# Relay_Control.net
KiCad netlist of a schematic drawn in Altium Designer
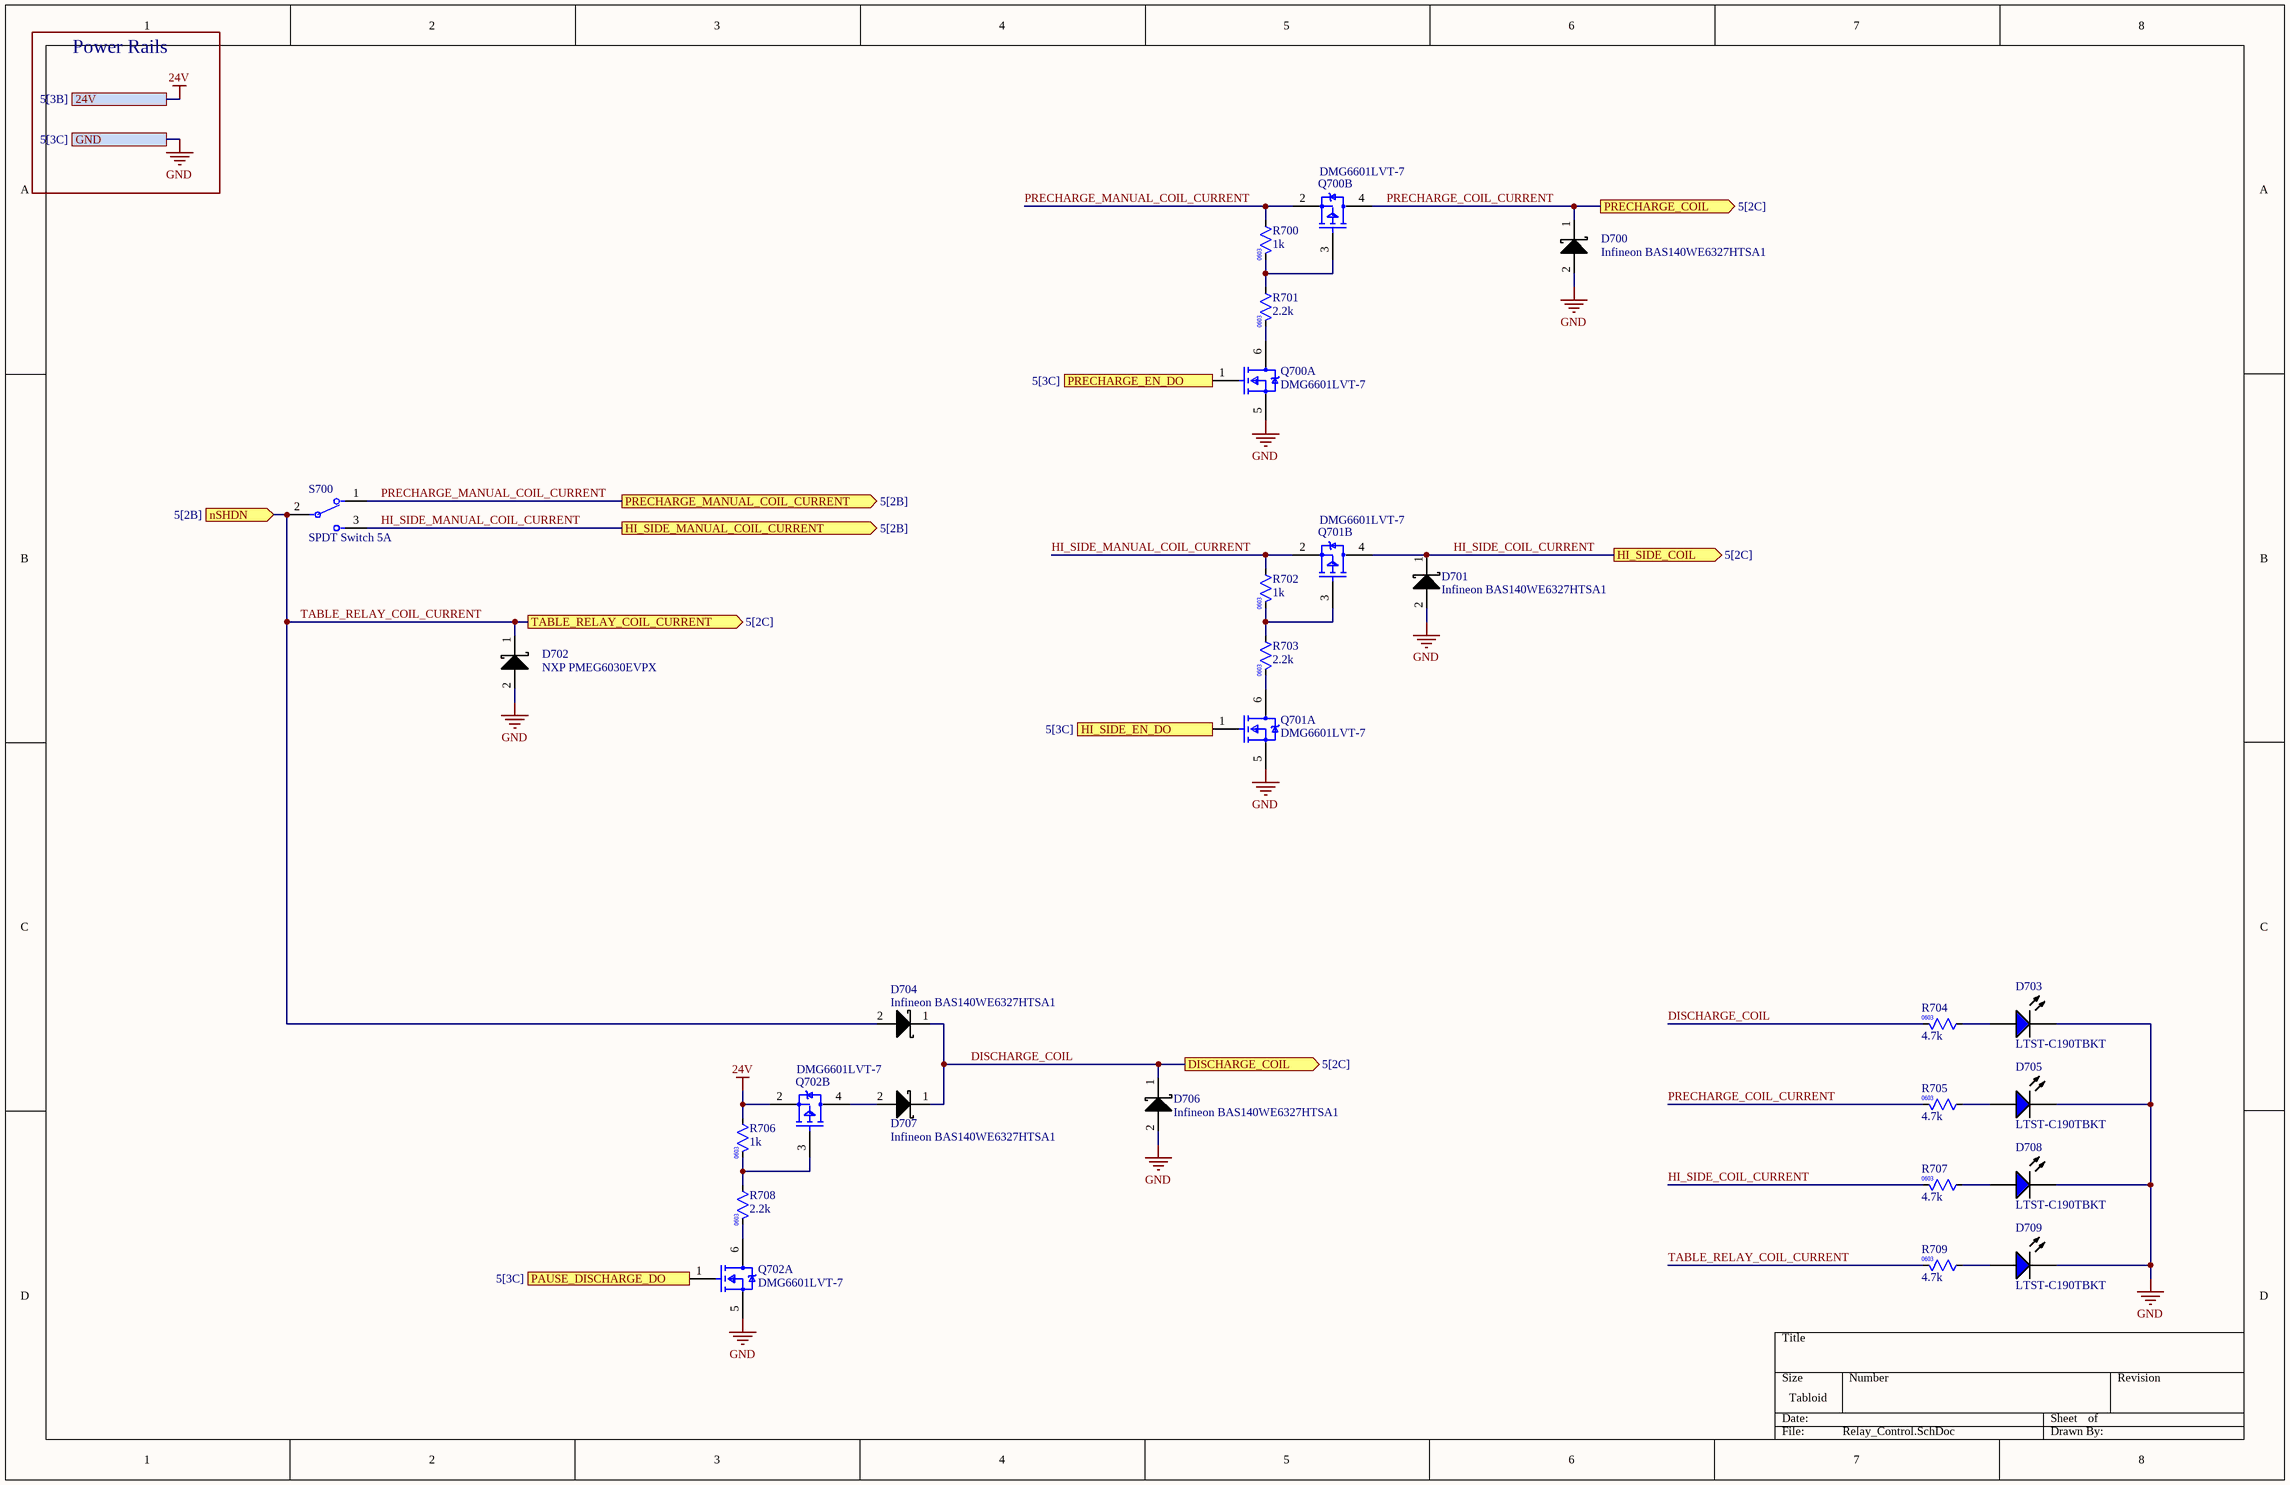
[diagram p0: Relay_Control.SchDoc]

(export (version "E")
  (design (tool "Eeschema 10.0.6"))
  (components
    (comp (ref "D700")
      (value "Infineon BAS140WE6327HTSA1")
      (footprint "INFINEON BAS140W SERIES")
      (description "DIODE SCHOTTKY 40V 120MA SOD323")
      (fields (field (name "SOURCE") "UBC Formula Electric.SchLib"))
      (libsource (lib "UBC Formula Electric") (part "Symbol"))
    )
    (comp (ref "D701")
      (value "Infineon BAS140WE6327HTSA1")
      (footprint "INFINEON BAS140W SERIES")
      (description "DIODE SCHOTTKY 40V 120MA SOD323")
      (fields (field (name "SOURCE") "UBC Formula Electric.SchLib"))
      (libsource (lib "UBC Formula Electric") (part "Symbol"))
    )
    (comp (ref "D702")
      (value "NXP PMEG6030EVPX")
      (footprint "NXP PMEG6030EVPX")
      (description "Diode Schottky 60V 3A Surface Mount SOD-128/CFP5")
      (fields (field (name "SOURCE") "Quad_Inverter.SchLib"))
      (libsource (lib "") (part "Symbol_1"))
    )
    (comp (ref "D703")
      (value "LTST-C190TBKT")
      (footprint "LTST-C190TBKT-2_V")
      (description "LED Uni-Color Blue, 76 mW, 20 mA, -20 to 80 degC, 2-Pin SMD, RoHS, Tape and Reel")
      (fields (field (name "MANUFACTURER") "Lite-On"))
      (libsource (lib "UBC Formula Electric") (part "LED-BLUE-AK-2"))
    )
    (comp (ref "D704")
      (value "Infineon BAS140WE6327HTSA1")
      (footprint "INFINEON BAS140W SERIES")
      (description "DIODE SCHOTTKY 40V 120MA SOD323")
      (fields (field (name "SOURCE") "UBC Formula Electric.SchLib"))
      (libsource (lib "UBC Formula Electric") (part "Symbol"))
    )
    (comp (ref "D705")
      (value "LTST-C190TBKT")
      (footprint "LTST-C190TBKT-2_V")
      (description "LED Uni-Color Blue, 76 mW, 20 mA, -20 to 80 degC, 2-Pin SMD, RoHS, Tape and Reel")
      (fields (field (name "MANUFACTURER") "Lite-On"))
      (libsource (lib "UBC Formula Electric") (part "LED-BLUE-AK-2"))
    )
    (comp (ref "D706")
      (value "Infineon BAS140WE6327HTSA1")
      (footprint "INFINEON BAS140W SERIES")
      (description "DIODE SCHOTTKY 40V 120MA SOD323")
      (fields (field (name "SOURCE") "UBC Formula Electric.SchLib"))
      (libsource (lib "UBC Formula Electric") (part "Symbol"))
    )
    (comp (ref "D707")
      (value "Infineon BAS140WE6327HTSA1")
      (footprint "INFINEON BAS140W SERIES")
      (description "DIODE SCHOTTKY 40V 120MA SOD323")
      (fields (field (name "SOURCE") "UBC Formula Electric.SchLib"))
      (libsource (lib "UBC Formula Electric") (part "Symbol"))
    )
    (comp (ref "D708")
      (value "LTST-C190TBKT")
      (footprint "LTST-C190TBKT-2_V")
      (description "LED Uni-Color Blue, 76 mW, 20 mA, -20 to 80 degC, 2-Pin SMD, RoHS, Tape and Reel")
      (fields (field (name "MANUFACTURER") "Lite-On"))
      (libsource (lib "UBC Formula Electric") (part "LED-BLUE-AK-2"))
    )
    (comp (ref "D709")
      (value "LTST-C190TBKT")
      (footprint "LTST-C190TBKT-2_V")
      (description "LED Uni-Color Blue, 76 mW, 20 mA, -20 to 80 degC, 2-Pin SMD, RoHS, Tape and Reel")
      (fields (field (name "MANUFACTURER") "Lite-On"))
      (libsource (lib "UBC Formula Electric") (part "LED-BLUE-AK-2"))
    )
    (comp (ref "Q700")
      (value "DMG6601LVT-7")
      (footprint "FP-TSOT26-IPC_A")
      (libsource (lib "UBC Formula Electric") (part "06fe37a93ab8884fb11e636f76dd7e0"))
    )
    (comp (ref "Q701")
      (value "DMG6601LVT-7")
      (footprint "FP-TSOT26-IPC_A")
      (libsource (lib "UBC Formula Electric") (part "06fe37a93ab8884fb11e636f76dd7e0"))
    )
    (comp (ref "Q702")
      (value "DMG6601LVT-7")
      (footprint "FP-TSOT26-IPC_A")
      (libsource (lib "UBC Formula Electric") (part "06fe37a93ab8884fb11e636f76dd7e0"))
    )
    (comp (ref "R700")
      (value "1k")
      (footprint "0603 Resistor Footprint")
      (description "RES SMD 1K OHM 1% 1/3W 0603")
      (fields (field (name "TOLERANCE") "1%") (field (name "POWER") "250mW"))
      (libsource (lib "UBC Formula Electric") (part "RES-2"))
    )
    (comp (ref "R701")
      (value "2.2k")
      (footprint "0603 Resistor Footprint")
      (description "RES SMD 2.2K OHM 1% 1/4W 0603")
      (fields
        (field (name "DIGIKEY PART NUMBER") "541-10449-1-ND")
        (field (name "MANUFACTURER PART NUMBER") "RCS06032K20FKEA")
      )
      (libsource (lib "UBC Formula Electric") (part "RES-2"))
    )
    (comp (ref "R702")
      (value "1k")
      (footprint "0603 Resistor Footprint")
      (description "RES SMD 1K OHM 1% 1/3W 0603")
      (fields (field (name "TOLERANCE") "1%") (field (name "POWER") "250mW"))
      (libsource (lib "UBC Formula Electric") (part "RES-2"))
    )
    (comp (ref "R703")
      (value "2.2k")
      (footprint "0603 Resistor Footprint")
      (description "RES SMD 2.2K OHM 1% 1/4W 0603")
      (fields
        (field (name "DIGIKEY PART NUMBER") "541-10449-1-ND")
        (field (name "MANUFACTURER PART NUMBER") "RCS06032K20FKEA")
      )
      (libsource (lib "UBC Formula Electric") (part "RES-2"))
    )
    (comp (ref "R704")
      (value "4.7k")
      (footprint "0603 Resistor Footprint")
      (description "RES SMD 4.7K OHM 1% 1/3W 0603")
      (fields (field (name "TOLERANCE") "1%") (field (name "POWER") "250mW"))
      (libsource (lib "UBC Formula Electric") (part "RES-2"))
    )
    (comp (ref "R705")
      (value "4.7k")
      (footprint "0603 Resistor Footprint")
      (description "RES SMD 4.7K OHM 1% 1/3W 0603")
      (fields (field (name "TOLERANCE") "1%") (field (name "POWER") "250mW"))
      (libsource (lib "UBC Formula Electric") (part "RES-2"))
    )
    (comp (ref "R706")
      (value "1k")
      (footprint "0603 Resistor Footprint")
      (description "RES SMD 1K OHM 1% 1/3W 0603")
      (fields (field (name "TOLERANCE") "1%") (field (name "POWER") "250mW"))
      (libsource (lib "UBC Formula Electric") (part "RES-2"))
    )
    (comp (ref "R707")
      (value "4.7k")
      (footprint "0603 Resistor Footprint")
      (description "RES SMD 4.7K OHM 1% 1/3W 0603")
      (fields (field (name "TOLERANCE") "1%") (field (name "POWER") "250mW"))
      (libsource (lib "UBC Formula Electric") (part "RES-2"))
    )
    (comp (ref "R708")
      (value "2.2k")
      (footprint "0603 Resistor Footprint")
      (description "RES SMD 2.2K OHM 1% 1/4W 0603")
      (fields
        (field (name "DIGIKEY PART NUMBER") "541-10449-1-ND")
        (field (name "MANUFACTURER PART NUMBER") "RCS06032K20FKEA")
      )
      (libsource (lib "UBC Formula Electric") (part "RES-2"))
    )
    (comp (ref "R709")
      (value "4.7k")
      (footprint "0603 Resistor Footprint")
      (description "RES SMD 4.7K OHM 1% 1/3W 0603")
      (fields (field (name "TOLERANCE") "1%") (field (name "POWER") "250mW"))
      (libsource (lib "UBC Formula Electric") (part "RES-2"))
    )
    (comp (ref "S700")
      (value "SPDT Switch 5A")
      (footprint "SPDT 5A")
      (libsource (lib "air_hockey_lib") (part "SPDT Switch 5A"))
    )
  )
  (nets
    (net (code "1") (name "/DISCHARGE_COIL") (class "Default")
      (node (ref "D704") (pin "1") (pinfunction "1_1") (pintype "passive"))
      (node (ref "D706") (pin "1") (pinfunction "1_1") (pintype "passive"))
      (node (ref "D707") (pin "1") (pinfunction "1_1") (pintype "passive"))
      (node (ref "R704") (pin "2") (pinfunction "2_2") (pintype "passive"))
    )
    (net (code "2") (name "/HI_SIDE_COIL_CURRENT") (class "Default")
      (node (ref "D701") (pin "1") (pinfunction "1_1") (pintype "passive"))
      (node (ref "Q701") (pin "4") (pinfunction "D2_4") (pintype "passive"))
      (node (ref "R707") (pin "2") (pinfunction "2_2") (pintype "passive"))
    )
    (net (code "3") (name "/HI_SIDE_EN_DO") (class "Default")
      (node (ref "Q701") (pin "1") (pinfunction "G1_1") (pintype "passive"))
    )
    (net (code "4") (name "/HI_SIDE_MANUAL_COIL_CURRENT") (class "Default")
      (node (ref "Q701") (pin "2") (pinfunction "S2_2") (pintype "passive"))
      (node (ref "R702") (pin "1") (pinfunction "1_1") (pintype "passive"))
      (node (ref "S700") (pin "3") (pinfunction "3_3") (pintype "passive"))
    )
    (net (code "5") (name "/PAUSE_DISCHARGE_DO") (class "Default")
      (node (ref "Q702") (pin "1") (pinfunction "G1_1") (pintype "passive"))
    )
    (net (code "6") (name "/PRECHARGE_COIL_CURRENT") (class "Default")
      (node (ref "D700") (pin "1") (pinfunction "1_1") (pintype "passive"))
      (node (ref "Q700") (pin "4") (pinfunction "D2_4") (pintype "passive"))
      (node (ref "R705") (pin "2") (pinfunction "2_2") (pintype "passive"))
    )
    (net (code "7") (name "/PRECHARGE_EN_DO") (class "Default")
      (node (ref "Q700") (pin "1") (pinfunction "G1_1") (pintype "passive"))
    )
    (net (code "8") (name "/PRECHARGE_MANUAL_COIL_CURRENT") (class "Default")
      (node (ref "Q700") (pin "2") (pinfunction "S2_2") (pintype "passive"))
      (node (ref "R700") (pin "1") (pinfunction "1_1") (pintype "passive"))
      (node (ref "S700") (pin "1") (pinfunction "1_1") (pintype "passive"))
    )
    (net (code "9") (name "/TABLE_RELAY_COIL_CURRENT") (class "Default")
      (node (ref "D702") (pin "1") (pinfunction "1_1") (pintype "passive"))
      (node (ref "D704") (pin "2") (pinfunction "2_2") (pintype "passive"))
      (node (ref "R709") (pin "2") (pinfunction "2_2") (pintype "passive"))
      (node (ref "S700") (pin "2") (pinfunction "2_2") (pintype "passive"))
    )
    (net (code "10") (name "24V") (class "Default")
      (node (ref "Q702") (pin "2") (pinfunction "S2_2") (pintype "passive"))
      (node (ref "R706") (pin "1") (pinfunction "1_1") (pintype "passive"))
    )
    (net (code "11") (name "GND") (class "Default")
      (node (ref "D700") (pin "2") (pinfunction "2_2") (pintype "passive"))
      (node (ref "D701") (pin "2") (pinfunction "2_2") (pintype "passive"))
      (node (ref "D702") (pin "2") (pinfunction "2_2") (pintype "passive"))
      (node (ref "D703") (pin "2") (pinfunction "K_2") (pintype "passive"))
      (node (ref "D705") (pin "2") (pinfunction "K_2") (pintype "passive"))
      (node (ref "D706") (pin "2") (pinfunction "2_2") (pintype "passive"))
      (node (ref "D708") (pin "2") (pinfunction "K_2") (pintype "passive"))
      (node (ref "D709") (pin "2") (pinfunction "K_2") (pintype "passive"))
      (node (ref "Q700") (pin "5") (pinfunction "S1_5") (pintype "passive"))
      (node (ref "Q701") (pin "5") (pinfunction "S1_5") (pintype "passive"))
      (node (ref "Q702") (pin "5") (pinfunction "S1_5") (pintype "passive"))
    )
    (net (code "12") (name "Net-(D703-A)") (class "Default")
      (node (ref "D703") (pin "1") (pinfunction "A_1") (pintype "passive"))
      (node (ref "R704") (pin "1") (pinfunction "1_1") (pintype "passive"))
    )
    (net (code "13") (name "Net-(D705-A)") (class "Default")
      (node (ref "D705") (pin "1") (pinfunction "A_1") (pintype "passive"))
      (node (ref "R705") (pin "1") (pinfunction "1_1") (pintype "passive"))
    )
    (net (code "14") (name "Net-(D708-A)") (class "Default")
      (node (ref "D708") (pin "1") (pinfunction "A_1") (pintype "passive"))
      (node (ref "R707") (pin "1") (pinfunction "1_1") (pintype "passive"))
    )
    (net (code "15") (name "Net-(D709-A)") (class "Default")
      (node (ref "D709") (pin "1") (pinfunction "A_1") (pintype "passive"))
      (node (ref "R709") (pin "1") (pinfunction "1_1") (pintype "passive"))
    )
    (net (code "16") (name "Net-(Q700A-D1)") (class "Default")
      (node (ref "Q700") (pin "6") (pinfunction "D1_6") (pintype "passive"))
      (node (ref "R701") (pin "2") (pinfunction "2_2") (pintype "passive"))
    )
    (net (code "17") (name "Net-(Q700B-G2)") (class "Default")
      (node (ref "Q700") (pin "3") (pinfunction "G2_3") (pintype "passive"))
      (node (ref "R700") (pin "2") (pinfunction "2_2") (pintype "passive"))
      (node (ref "R701") (pin "1") (pinfunction "1_1") (pintype "passive"))
    )
    (net (code "18") (name "Net-(Q701A-D1)") (class "Default")
      (node (ref "Q701") (pin "6") (pinfunction "D1_6") (pintype "passive"))
      (node (ref "R703") (pin "2") (pinfunction "2_2") (pintype "passive"))
    )
    (net (code "19") (name "Net-(Q701B-G2)") (class "Default")
      (node (ref "Q701") (pin "3") (pinfunction "G2_3") (pintype "passive"))
      (node (ref "R702") (pin "2") (pinfunction "2_2") (pintype "passive"))
      (node (ref "R703") (pin "1") (pinfunction "1_1") (pintype "passive"))
    )
    (net (code "20") (name "Net-(Q702A-D1)") (class "Default")
      (node (ref "Q702") (pin "6") (pinfunction "D1_6") (pintype "passive"))
      (node (ref "R708") (pin "2") (pinfunction "2_2") (pintype "passive"))
    )
    (net (code "21") (name "Net-(Q702B-D2)") (class "Default")
      (node (ref "D707") (pin "2") (pinfunction "2_2") (pintype "passive"))
      (node (ref "Q702") (pin "4") (pinfunction "D2_4") (pintype "passive"))
    )
    (net (code "22") (name "Net-(Q702B-G2)") (class "Default")
      (node (ref "Q702") (pin "3") (pinfunction "G2_3") (pintype "passive"))
      (node (ref "R706") (pin "2") (pinfunction "2_2") (pintype "passive"))
      (node (ref "R708") (pin "1") (pinfunction "1_1") (pintype "passive"))
    )
  )
)
